# Regulator.net
KiCad netlist of a schematic drawn in Altium Designer
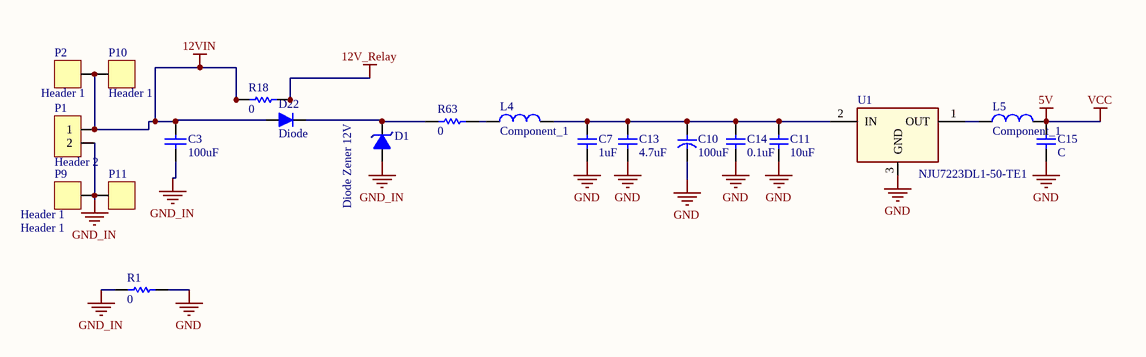
[diagram p0: Regulator.SchDoc]

(export (version "E")
  (design (tool "Eeschema 10.0.6"))
  (components
    (comp (ref "C3")
      (value "100uF")
      (footprint "Cap Non-Pol 5mm")
      (description "Non-polarized Capacitor")
      (fields (field (name "Comment") "Cap Non-pol") (field (name "PUBLISHER") "Altium Limited"))
      (libsource (lib "phong") (part "Cap Non-pol"))
    )
    (comp (ref "C7")
      (value "1uF")
      (footprint "C 0805 (2012)")
      (description "Capacitor non-pol")
      (libsource (lib "BKIT4U_LIB") (part "Capacitor NP"))
    )
    (comp (ref "C10")
      (value "100uF")
      (footprint "C SMD ALU (B)")
      (description "Capacitor pol")
      (libsource (lib "ChipFC_Lib") (part "Capacitor"))
    )
    (comp (ref "C11")
      (value "10uF")
      (footprint "C 0805")
      (description "Capacitor non-pol")
      (libsource (lib "BKIT4U_LIB") (part "Capacitor NP"))
    )
    (comp (ref "C13")
      (value "4.7uF")
      (footprint "C 0805 (2012)")
      (description "Capacitor non-pol")
      (libsource (lib "BKIT4U_LIB") (part "Capacitor NP"))
    )
    (comp (ref "C14")
      (value "0.1uF")
      (footprint "C 0805")
      (description "Capacitor non-pol")
      (libsource (lib "BKIT4U_LIB") (part "Capacitor NP"))
    )
    (comp (ref "C15")
      (value "C")
      (footprint "C 0805")
      (description "Capacitor non-pol")
      (libsource (lib "BKIT4U_LIB") (part "Capacitor NP"))
    )
    (comp (ref "D1")
      (value "Diode Zener 12V")
      (footprint "DO-214AC (SMA)")
      (libsource (lib "syhaunguyen") (part "Zener"))
    )
    (comp (ref "D22")
      (value "Diode")
      (footprint "DO-214AC (SMA)")
      (description "Default Diode")
      (libsource (lib "ChipFC_Lib") (part "Diode"))
    )
    (comp (ref "L4")
      (value "Component_1")
      (footprint "C 1210")
      (libsource (lib "Integrated_Library1") (part "Component_1"))
    )
    (comp (ref "L5")
      (value "Component_1")
      (footprint "C 1210")
      (libsource (lib "Integrated_Library1") (part "Component_1"))
    )
    (comp (ref "P1")
      (value "Header 2")
      (footprint "HDR Domino 2")
      (description "Header, 2-Pin")
      (fields (field (name "PUBLISHER") "Altium Limited"))
      (libsource (lib "BKIT4U_LIB") (part "Header 2"))
    )
    (comp (ref "P2")
      (value "Header 1")
      (footprint "HDR/Terminal/1/screw")
      (description "Header, 1-Pin")
      (libsource (lib "") (part "Header 1_1"))
    )
    (comp (ref "P9")
      (value "Header 1")
      (footprint "HDR/Terminal/1/screw")
      (description "Header, 1-Pin")
      (libsource (lib "") (part "Header 1_1"))
    )
    (comp (ref "P10")
      (value "Header 1")
      (footprint "HDR/Terminal/1/copper/6.0")
      (description "Header, 1-Pin")
      (libsource (lib "chipfc_altium_libs") (part "Header 1"))
    )
    (comp (ref "P11")
      (value "Header 1")
      (footprint "HDR/Terminal/1/copper/6.0")
      (description "Header, 1-Pin")
      (libsource (lib "chipfc_altium_libs") (part "Header 1"))
    )
    (comp (ref "R1")
      (value "0")
      (footprint "R 0805")
      (description "Resistor")
      (fields (field (name "PUBLISHER") "Altium Limited"))
      (libsource (lib "BKIT4U_LIB") (part "Resistor"))
    )
    (comp (ref "R18")
      (value "0")
      (footprint "R 0805 (2012)")
      (description "Resistor")
      (fields (field (name "PUBLISHER") "Altium Limited"))
      (libsource (lib "BKIT4U_LIB") (part "Resistor"))
    )
    (comp (ref "R63")
      (value "0")
      (footprint "R 0805")
      (description "Resistor")
      (fields (field (name "PUBLISHER") "Altium Limited"))
      (libsource (lib "BKIT4U_LIB") (part "Resistor"))
    )
    (comp (ref "U1")
      (value "NJU7223DL1-50-TE1")
      (footprint "TO-252 (DPAK)")
      (description "LDO Fixed Voltage regulator")
      (libsource (lib "BKIT4U_LIB") (part "78xx"))
    )
  )
  (nets
    (net (code "1") (name "5V") (class "Default")
      (node (ref "C15") (pin "1") (pinfunction "1_1") (pintype "passive"))
      (node (ref "L5") (pin "2") (pinfunction "2_2") (pintype "passive"))
    )
    (net (code "2") (name "12VIN") (class "Default")
      (node (ref "C3") (pin "2") (pinfunction "2_2") (pintype "passive"))
      (node (ref "D22") (pin "1") (pinfunction "A_1") (pintype "passive"))
      (node (ref "P1") (pin "1") (pinfunction "1_1") (pintype "passive"))
      (node (ref "P10") (pin "1") (pinfunction "1_1") (pintype "passive"))
      (node (ref "P2") (pin "1") (pinfunction "1_1") (pintype "passive"))
      (node (ref "R18") (pin "1") (pinfunction "1_1") (pintype "passive"))
    )
    (net (code "3") (name "12V_Relay") (class "Default")
      (node (ref "R18") (pin "2") (pinfunction "2_2") (pintype "passive"))
    )
    (net (code "4") (name "GND") (class "Default")
      (node (ref "C10") (pin "2") (pinfunction "2_2") (pintype "passive"))
      (node (ref "C11") (pin "2") (pinfunction "2_2") (pintype "passive"))
      (node (ref "C13") (pin "2") (pinfunction "2_2") (pintype "passive"))
      (node (ref "C14") (pin "2") (pinfunction "2_2") (pintype "passive"))
      (node (ref "C15") (pin "2") (pinfunction "2_2") (pintype "passive"))
      (node (ref "C7") (pin "2") (pinfunction "2_2") (pintype "passive"))
      (node (ref "R1") (pin "1") (pinfunction "1_1") (pintype "passive"))
      (node (ref "U1") (pin "3") (pinfunction "GND_3") (pintype "passive"))
    )
    (net (code "5") (name "GND_IN") (class "Default")
      (node (ref "C3") (pin "1") (pinfunction "1_1") (pintype "passive"))
      (node (ref "D1") (pin "1") (pinfunction "A_1") (pintype "passive"))
      (node (ref "P1") (pin "2") (pinfunction "2_2") (pintype "passive"))
      (node (ref "P11") (pin "1") (pinfunction "1_1") (pintype "passive"))
      (node (ref "P9") (pin "1") (pinfunction "1_1") (pintype "passive"))
      (node (ref "R1") (pin "2") (pinfunction "2_2") (pintype "passive"))
    )
    (net (code "6") (name "Net-(D1-K)") (class "Default")
      (node (ref "D1") (pin "2") (pinfunction "K_2") (pintype "passive"))
      (node (ref "D22") (pin "2") (pinfunction "K_2") (pintype "passive"))
      (node (ref "R63") (pin "2") (pinfunction "2_2") (pintype "passive"))
    )
    (net (code "7") (name "Net-(L4-Pad1)") (class "Default")
      (node (ref "L4") (pin "1") (pinfunction "1_1") (pintype "passive"))
      (node (ref "R63") (pin "1") (pinfunction "1_1") (pintype "passive"))
    )
    (net (code "8") (name "Net-(U1-IN)") (class "Default")
      (node (ref "C10") (pin "1") (pinfunction "1_1") (pintype "passive"))
      (node (ref "C11") (pin "1") (pinfunction "1_1") (pintype "passive"))
      (node (ref "C13") (pin "1") (pinfunction "1_1") (pintype "passive"))
      (node (ref "C14") (pin "1") (pinfunction "1_1") (pintype "passive"))
      (node (ref "C7") (pin "1") (pinfunction "1_1") (pintype "passive"))
      (node (ref "L4") (pin "2") (pinfunction "2_2") (pintype "passive"))
      (node (ref "U1") (pin "2") (pinfunction "IN_2") (pintype "power_in"))
    )
    (net (code "9") (name "Net-(U1-OUT)") (class "Default")
      (node (ref "L5") (pin "1") (pinfunction "1_1") (pintype "passive"))
      (node (ref "U1") (pin "1") (pinfunction "OUT_1") (pintype "passive"))
    )
  )
)
